# shield_2016.net
KiCad netlist of a schematic drawn in EAGLE
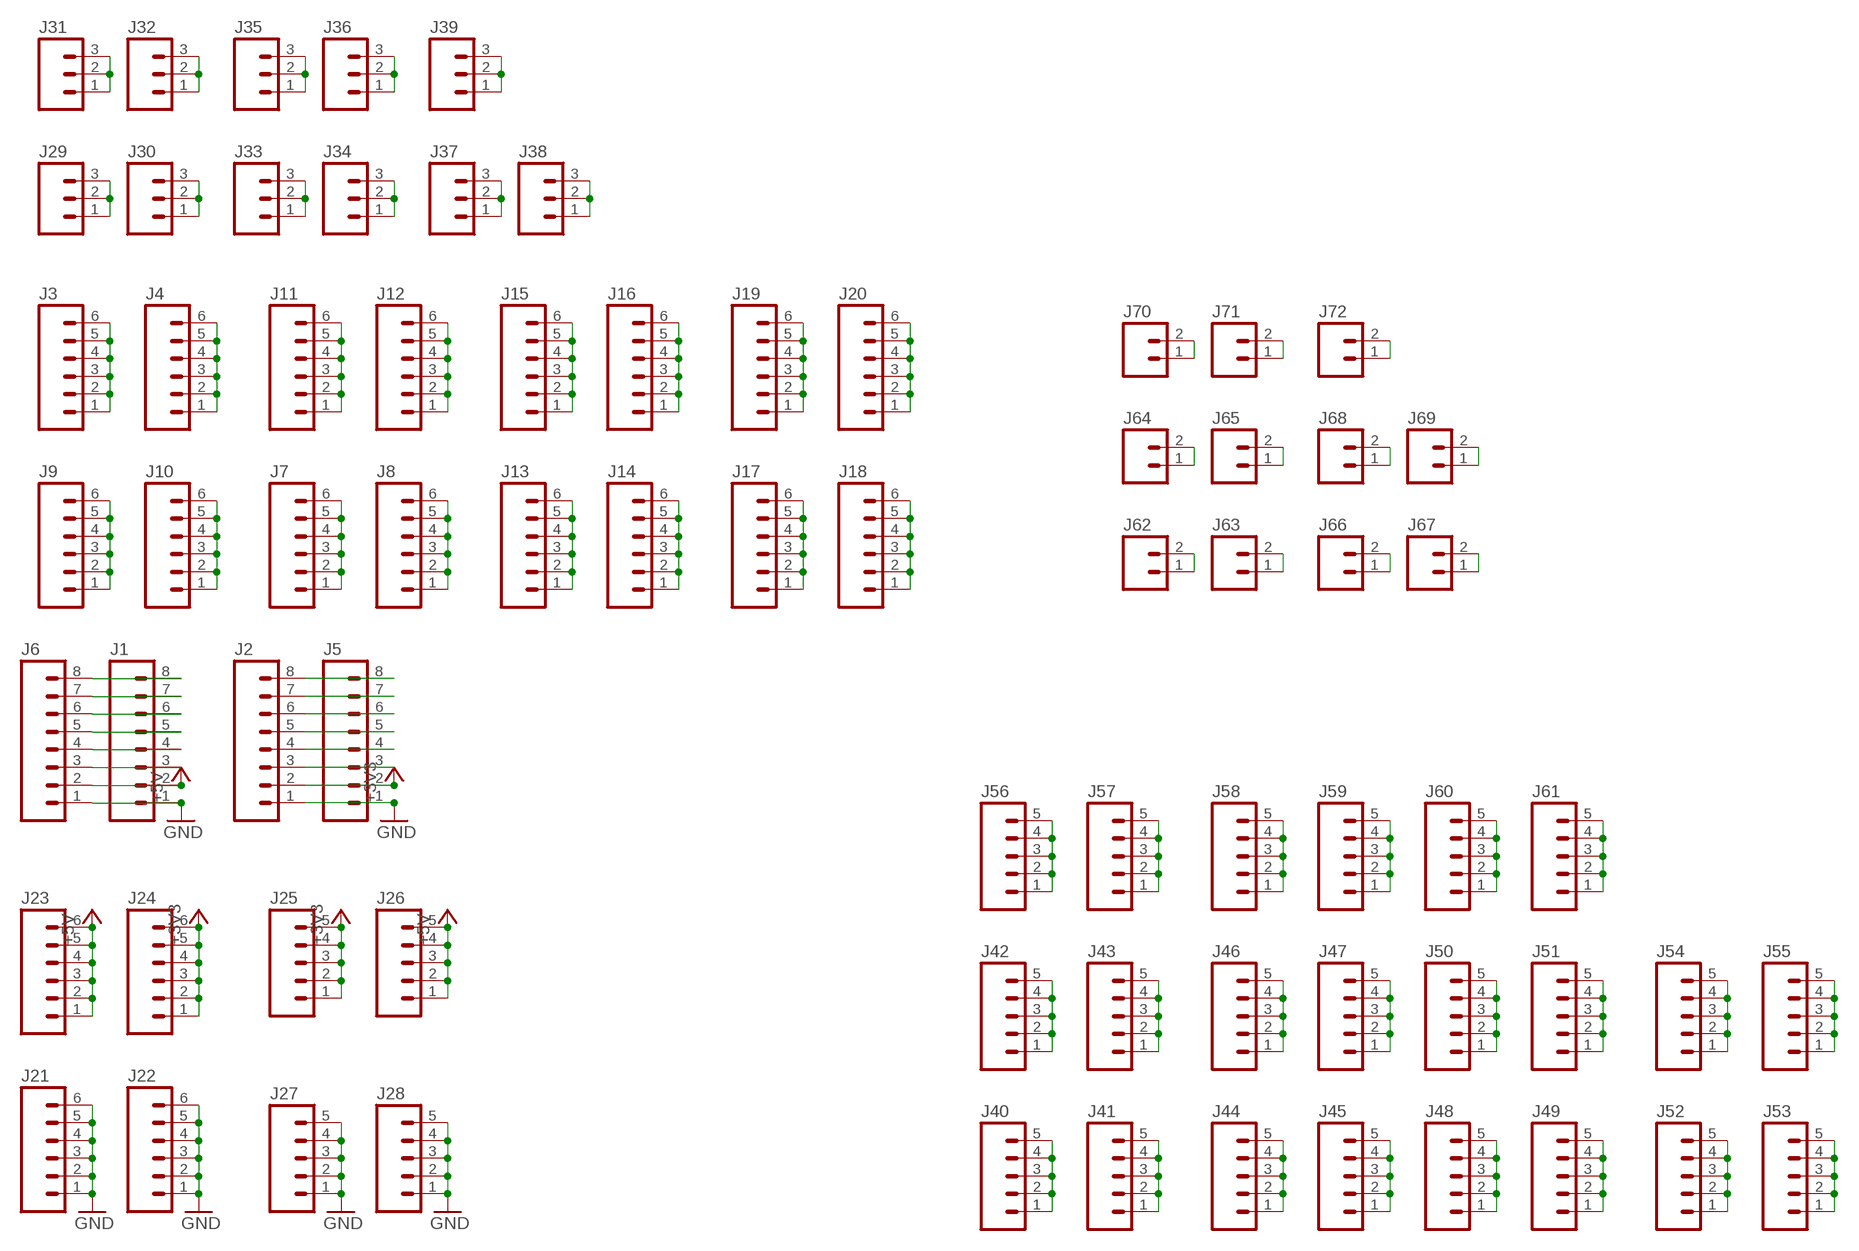
[diagram p0: schematic, sheet 1]

(export (version "E")
  (design (tool "Eeschema 10.0.6"))
  (components
    (comp (ref "J1")
      (value "M08")
      (footprint "eagle-import:1X08_ROUND")
      (libsource (lib "eagle-import") (part "M08"))
    )
    (comp (ref "J2")
      (value "M08")
      (footprint "eagle-import:1X08_ROUND")
      (libsource (lib "eagle-import") (part "M08"))
    )
    (comp (ref "J3")
      (value "M06SILK_FEMALE_PTH")
      (footprint "eagle-import:1X06")
      (libsource (lib "eagle-import") (part "M06SILK_FEMALE_PTH"))
    )
    (comp (ref "J4")
      (value "M06SILK_FEMALE_PTH")
      (footprint "eagle-import:1X06")
      (libsource (lib "eagle-import") (part "M06SILK_FEMALE_PTH"))
    )
    (comp (ref "J5")
      (value "M08")
      (footprint "eagle-import:1X08_ROUND")
      (libsource (lib "eagle-import") (part "M08"))
    )
    (comp (ref "J6")
      (value "M08")
      (footprint "eagle-import:1X08_ROUND")
      (libsource (lib "eagle-import") (part "M08"))
    )
    (comp (ref "J7")
      (value "M06SILK_FEMALE_PTH")
      (footprint "eagle-import:1X06")
      (libsource (lib "eagle-import") (part "M06SILK_FEMALE_PTH"))
    )
    (comp (ref "J8")
      (value "M06SILK_FEMALE_PTH")
      (footprint "eagle-import:1X06")
      (libsource (lib "eagle-import") (part "M06SILK_FEMALE_PTH"))
    )
    (comp (ref "J9")
      (value "M06SILK_FEMALE_PTH")
      (footprint "eagle-import:1X06")
      (libsource (lib "eagle-import") (part "M06SILK_FEMALE_PTH"))
    )
    (comp (ref "J10")
      (value "M06SILK_FEMALE_PTH")
      (footprint "eagle-import:1X06")
      (libsource (lib "eagle-import") (part "M06SILK_FEMALE_PTH"))
    )
    (comp (ref "J11")
      (value "M06SILK_FEMALE_PTH")
      (footprint "eagle-import:1X06")
      (libsource (lib "eagle-import") (part "M06SILK_FEMALE_PTH"))
    )
    (comp (ref "J12")
      (value "M06SILK_FEMALE_PTH")
      (footprint "eagle-import:1X06")
      (libsource (lib "eagle-import") (part "M06SILK_FEMALE_PTH"))
    )
    (comp (ref "J13")
      (value "M06SILK_FEMALE_PTH")
      (footprint "eagle-import:1X06")
      (libsource (lib "eagle-import") (part "M06SILK_FEMALE_PTH"))
    )
    (comp (ref "J14")
      (value "M06SILK_FEMALE_PTH")
      (footprint "eagle-import:1X06")
      (libsource (lib "eagle-import") (part "M06SILK_FEMALE_PTH"))
    )
    (comp (ref "J15")
      (value "M06SILK_FEMALE_PTH")
      (footprint "eagle-import:1X06")
      (libsource (lib "eagle-import") (part "M06SILK_FEMALE_PTH"))
    )
    (comp (ref "J16")
      (value "M06SILK_FEMALE_PTH")
      (footprint "eagle-import:1X06")
      (libsource (lib "eagle-import") (part "M06SILK_FEMALE_PTH"))
    )
    (comp (ref "J17")
      (value "M06SILK_FEMALE_PTH")
      (footprint "eagle-import:1X06")
      (libsource (lib "eagle-import") (part "M06SILK_FEMALE_PTH"))
    )
    (comp (ref "J18")
      (value "M06SILK_FEMALE_PTH")
      (footprint "eagle-import:1X06")
      (libsource (lib "eagle-import") (part "M06SILK_FEMALE_PTH"))
    )
    (comp (ref "J19")
      (value "M06SILK_FEMALE_PTH")
      (footprint "eagle-import:1X06")
      (libsource (lib "eagle-import") (part "M06SILK_FEMALE_PTH"))
    )
    (comp (ref "J20")
      (value "M06SILK_FEMALE_PTH")
      (footprint "eagle-import:1X06")
      (libsource (lib "eagle-import") (part "M06SILK_FEMALE_PTH"))
    )
    (comp (ref "J21")
      (value "M06SILK_FEMALE_PTH")
      (footprint "eagle-import:1X06")
      (libsource (lib "eagle-import") (part "M06SILK_FEMALE_PTH"))
    )
    (comp (ref "J22")
      (value "M06SILK_FEMALE_PTH")
      (footprint "eagle-import:1X06")
      (libsource (lib "eagle-import") (part "M06SILK_FEMALE_PTH"))
    )
    (comp (ref "J23")
      (value "M06SILK_FEMALE_PTH")
      (footprint "eagle-import:1X06")
      (libsource (lib "eagle-import") (part "M06SILK_FEMALE_PTH"))
    )
    (comp (ref "J24")
      (value "M06SILK_FEMALE_PTH")
      (footprint "eagle-import:1X06")
      (libsource (lib "eagle-import") (part "M06SILK_FEMALE_PTH"))
    )
    (comp (ref "J25")
      (value "M05PTH")
      (footprint "eagle-import:1X05")
      (libsource (lib "eagle-import") (part "M05PTH"))
    )
    (comp (ref "J26")
      (value "M05PTH")
      (footprint "eagle-import:1X05")
      (libsource (lib "eagle-import") (part "M05PTH"))
    )
    (comp (ref "J27")
      (value "M05PTH")
      (footprint "eagle-import:1X05")
      (libsource (lib "eagle-import") (part "M05PTH"))
    )
    (comp (ref "J28")
      (value "M05PTH")
      (footprint "eagle-import:1X05")
      (libsource (lib "eagle-import") (part "M05PTH"))
    )
    (comp (ref "J29")
      (value "M03PTH")
      (footprint "eagle-import:1X03")
      (libsource (lib "eagle-import") (part "M03PTH"))
    )
    (comp (ref "J30")
      (value "M03PTH")
      (footprint "eagle-import:1X03")
      (libsource (lib "eagle-import") (part "M03PTH"))
    )
    (comp (ref "J31")
      (value "M03PTH")
      (footprint "eagle-import:1X03")
      (libsource (lib "eagle-import") (part "M03PTH"))
    )
    (comp (ref "J32")
      (value "M03PTH")
      (footprint "eagle-import:1X03")
      (libsource (lib "eagle-import") (part "M03PTH"))
    )
    (comp (ref "J33")
      (value "M03PTH")
      (footprint "eagle-import:1X03")
      (libsource (lib "eagle-import") (part "M03PTH"))
    )
    (comp (ref "J34")
      (value "M03PTH")
      (footprint "eagle-import:1X03")
      (libsource (lib "eagle-import") (part "M03PTH"))
    )
    (comp (ref "J35")
      (value "M03PTH")
      (footprint "eagle-import:1X03")
      (libsource (lib "eagle-import") (part "M03PTH"))
    )
    (comp (ref "J36")
      (value "M03PTH")
      (footprint "eagle-import:1X03")
      (libsource (lib "eagle-import") (part "M03PTH"))
    )
    (comp (ref "J37")
      (value "M03PTH")
      (footprint "eagle-import:1X03")
      (libsource (lib "eagle-import") (part "M03PTH"))
    )
    (comp (ref "J38")
      (value "M03PTH")
      (footprint "eagle-import:1X03")
      (libsource (lib "eagle-import") (part "M03PTH"))
    )
    (comp (ref "J39")
      (value "M03PTH")
      (footprint "eagle-import:1X03")
      (libsource (lib "eagle-import") (part "M03PTH"))
    )
    (comp (ref "J40")
      (value "M05PTH")
      (footprint "eagle-import:1X05")
      (libsource (lib "eagle-import") (part "M05PTH"))
    )
    (comp (ref "J41")
      (value "M05PTH")
      (footprint "eagle-import:1X05")
      (libsource (lib "eagle-import") (part "M05PTH"))
    )
    (comp (ref "J42")
      (value "M05PTH")
      (footprint "eagle-import:1X05")
      (libsource (lib "eagle-import") (part "M05PTH"))
    )
    (comp (ref "J43")
      (value "M05PTH")
      (footprint "eagle-import:1X05")
      (libsource (lib "eagle-import") (part "M05PTH"))
    )
    (comp (ref "J44")
      (value "M05PTH")
      (footprint "eagle-import:1X05")
      (libsource (lib "eagle-import") (part "M05PTH"))
    )
    (comp (ref "J45")
      (value "M05PTH")
      (footprint "eagle-import:1X05")
      (libsource (lib "eagle-import") (part "M05PTH"))
    )
    (comp (ref "J46")
      (value "M05PTH")
      (footprint "eagle-import:1X05")
      (libsource (lib "eagle-import") (part "M05PTH"))
    )
    (comp (ref "J47")
      (value "M05PTH")
      (footprint "eagle-import:1X05")
      (libsource (lib "eagle-import") (part "M05PTH"))
    )
    (comp (ref "J48")
      (value "M05PTH")
      (footprint "eagle-import:1X05")
      (libsource (lib "eagle-import") (part "M05PTH"))
    )
    (comp (ref "J49")
      (value "M05PTH")
      (footprint "eagle-import:1X05")
      (libsource (lib "eagle-import") (part "M05PTH"))
    )
    (comp (ref "J50")
      (value "M05PTH")
      (footprint "eagle-import:1X05")
      (libsource (lib "eagle-import") (part "M05PTH"))
    )
    (comp (ref "J51")
      (value "M05PTH")
      (footprint "eagle-import:1X05")
      (libsource (lib "eagle-import") (part "M05PTH"))
    )
    (comp (ref "J52")
      (value "M05PTH")
      (footprint "eagle-import:1X05")
      (libsource (lib "eagle-import") (part "M05PTH"))
    )
    (comp (ref "J53")
      (value "M05PTH")
      (footprint "eagle-import:1X05")
      (libsource (lib "eagle-import") (part "M05PTH"))
    )
    (comp (ref "J54")
      (value "M05PTH")
      (footprint "eagle-import:1X05")
      (libsource (lib "eagle-import") (part "M05PTH"))
    )
    (comp (ref "J55")
      (value "M05PTH")
      (footprint "eagle-import:1X05")
      (libsource (lib "eagle-import") (part "M05PTH"))
    )
    (comp (ref "J56")
      (value "M05PTH")
      (footprint "eagle-import:1X05")
      (libsource (lib "eagle-import") (part "M05PTH"))
    )
    (comp (ref "J57")
      (value "M05PTH")
      (footprint "eagle-import:1X05")
      (libsource (lib "eagle-import") (part "M05PTH"))
    )
    (comp (ref "J58")
      (value "M05PTH")
      (footprint "eagle-import:1X05")
      (libsource (lib "eagle-import") (part "M05PTH"))
    )
    (comp (ref "J59")
      (value "M05PTH")
      (footprint "eagle-import:1X05")
      (libsource (lib "eagle-import") (part "M05PTH"))
    )
    (comp (ref "J60")
      (value "M05PTH")
      (footprint "eagle-import:1X05")
      (libsource (lib "eagle-import") (part "M05PTH"))
    )
    (comp (ref "J61")
      (value "M05PTH")
      (footprint "eagle-import:1X05")
      (libsource (lib "eagle-import") (part "M05PTH"))
    )
    (comp (ref "J62")
      (value "M02PTH")
      (footprint "eagle-import:1X02")
      (libsource (lib "eagle-import") (part "M02PTH"))
    )
    (comp (ref "J63")
      (value "M02PTH")
      (footprint "eagle-import:1X02")
      (libsource (lib "eagle-import") (part "M02PTH"))
    )
    (comp (ref "J64")
      (value "M02PTH")
      (footprint "eagle-import:1X02")
      (libsource (lib "eagle-import") (part "M02PTH"))
    )
    (comp (ref "J65")
      (value "M02PTH")
      (footprint "eagle-import:1X02")
      (libsource (lib "eagle-import") (part "M02PTH"))
    )
    (comp (ref "J66")
      (value "M02PTH")
      (footprint "eagle-import:1X02")
      (libsource (lib "eagle-import") (part "M02PTH"))
    )
    (comp (ref "J67")
      (value "M02PTH")
      (footprint "eagle-import:1X02")
      (libsource (lib "eagle-import") (part "M02PTH"))
    )
    (comp (ref "J68")
      (value "M02PTH")
      (footprint "eagle-import:1X02")
      (libsource (lib "eagle-import") (part "M02PTH"))
    )
    (comp (ref "J69")
      (value "M02PTH")
      (footprint "eagle-import:1X02")
      (libsource (lib "eagle-import") (part "M02PTH"))
    )
    (comp (ref "J70")
      (value "M02PTH")
      (footprint "eagle-import:1X02")
      (libsource (lib "eagle-import") (part "M02PTH"))
    )
    (comp (ref "J71")
      (value "M02PTH")
      (footprint "eagle-import:1X02")
      (libsource (lib "eagle-import") (part "M02PTH"))
    )
    (comp (ref "J72")
      (value "M02PTH")
      (footprint "eagle-import:1X02")
      (libsource (lib "eagle-import") (part "M02PTH"))
    )
  )
  (nets
    (net (code "1") (name "+3V3") (class "Default")
      (node (ref "J2") (pin "2") (pinfunction "2_2") (pintype "passive"))
      (node (ref "J24") (pin "1") (pinfunction "1_1") (pintype "passive"))
      (node (ref "J24") (pin "2") (pinfunction "2_2") (pintype "passive"))
      (node (ref "J24") (pin "3") (pinfunction "3_3") (pintype "passive"))
      (node (ref "J24") (pin "4") (pinfunction "4_4") (pintype "passive"))
      (node (ref "J24") (pin "5") (pinfunction "5_5") (pintype "passive"))
      (node (ref "J24") (pin "6") (pinfunction "6_6") (pintype "passive"))
      (node (ref "J25") (pin "1") (pinfunction "1_1") (pintype "passive"))
      (node (ref "J25") (pin "2") (pinfunction "2_2") (pintype "passive"))
      (node (ref "J25") (pin "3") (pinfunction "3_3") (pintype "passive"))
      (node (ref "J25") (pin "4") (pinfunction "4_4") (pintype "passive"))
      (node (ref "J25") (pin "5") (pinfunction "5_5") (pintype "passive"))
      (node (ref "J5") (pin "2") (pinfunction "2_2") (pintype "passive"))
    )
    (net (code "2") (name "+5V") (class "Default")
      (node (ref "J1") (pin "2") (pinfunction "2_2") (pintype "passive"))
      (node (ref "J23") (pin "1") (pinfunction "1_1") (pintype "passive"))
      (node (ref "J23") (pin "2") (pinfunction "2_2") (pintype "passive"))
      (node (ref "J23") (pin "3") (pinfunction "3_3") (pintype "passive"))
      (node (ref "J23") (pin "4") (pinfunction "4_4") (pintype "passive"))
      (node (ref "J23") (pin "5") (pinfunction "5_5") (pintype "passive"))
      (node (ref "J23") (pin "6") (pinfunction "6_6") (pintype "passive"))
      (node (ref "J26") (pin "1") (pinfunction "1_1") (pintype "passive"))
      (node (ref "J26") (pin "2") (pinfunction "2_2") (pintype "passive"))
      (node (ref "J26") (pin "3") (pinfunction "3_3") (pintype "passive"))
      (node (ref "J26") (pin "4") (pinfunction "4_4") (pintype "passive"))
      (node (ref "J26") (pin "5") (pinfunction "5_5") (pintype "passive"))
      (node (ref "J6") (pin "2") (pinfunction "2_2") (pintype "passive"))
    )
    (net (code "3") (name "GND") (class "Default")
      (node (ref "J1") (pin "1") (pinfunction "1_1") (pintype "passive"))
      (node (ref "J2") (pin "1") (pinfunction "1_1") (pintype "passive"))
      (node (ref "J21") (pin "1") (pinfunction "1_1") (pintype "passive"))
      (node (ref "J21") (pin "2") (pinfunction "2_2") (pintype "passive"))
      (node (ref "J21") (pin "3") (pinfunction "3_3") (pintype "passive"))
      (node (ref "J21") (pin "4") (pinfunction "4_4") (pintype "passive"))
      (node (ref "J21") (pin "5") (pinfunction "5_5") (pintype "passive"))
      (node (ref "J21") (pin "6") (pinfunction "6_6") (pintype "passive"))
      (node (ref "J22") (pin "1") (pinfunction "1_1") (pintype "passive"))
      (node (ref "J22") (pin "2") (pinfunction "2_2") (pintype "passive"))
      (node (ref "J22") (pin "3") (pinfunction "3_3") (pintype "passive"))
      (node (ref "J22") (pin "4") (pinfunction "4_4") (pintype "passive"))
      (node (ref "J22") (pin "5") (pinfunction "5_5") (pintype "passive"))
      (node (ref "J22") (pin "6") (pinfunction "6_6") (pintype "passive"))
      (node (ref "J27") (pin "1") (pinfunction "1_1") (pintype "passive"))
      (node (ref "J27") (pin "2") (pinfunction "2_2") (pintype "passive"))
      (node (ref "J27") (pin "3") (pinfunction "3_3") (pintype "passive"))
      (node (ref "J27") (pin "4") (pinfunction "4_4") (pintype "passive"))
      (node (ref "J27") (pin "5") (pinfunction "5_5") (pintype "passive"))
      (node (ref "J28") (pin "1") (pinfunction "1_1") (pintype "passive"))
      (node (ref "J28") (pin "2") (pinfunction "2_2") (pintype "passive"))
      (node (ref "J28") (pin "3") (pinfunction "3_3") (pintype "passive"))
      (node (ref "J28") (pin "4") (pinfunction "4_4") (pintype "passive"))
      (node (ref "J28") (pin "5") (pinfunction "5_5") (pintype "passive"))
      (node (ref "J5") (pin "1") (pinfunction "1_1") (pintype "passive"))
      (node (ref "J6") (pin "1") (pinfunction "1_1") (pintype "passive"))
    )
    (net (code "4") (name "Net-(J1-Pad3)") (class "Default")
      (node (ref "J1") (pin "3") (pinfunction "3_3") (pintype "passive"))
      (node (ref "J6") (pin "3") (pinfunction "3_3") (pintype "passive"))
    )
    (net (code "5") (name "Net-(J1-Pad4)") (class "Default")
      (node (ref "J1") (pin "4") (pinfunction "4_4") (pintype "passive"))
      (node (ref "J6") (pin "4") (pinfunction "4_4") (pintype "passive"))
    )
    (net (code "6") (name "Net-(J1-Pad5)") (class "Default")
      (node (ref "J1") (pin "5") (pinfunction "5_5") (pintype "passive"))
      (node (ref "J6") (pin "5") (pinfunction "5_5") (pintype "passive"))
    )
    (net (code "7") (name "Net-(J1-Pad6)") (class "Default")
      (node (ref "J1") (pin "6") (pinfunction "6_6") (pintype "passive"))
      (node (ref "J6") (pin "6") (pinfunction "6_6") (pintype "passive"))
    )
    (net (code "8") (name "Net-(J1-Pad7)") (class "Default")
      (node (ref "J1") (pin "7") (pinfunction "7_7") (pintype "passive"))
      (node (ref "J6") (pin "7") (pinfunction "7_7") (pintype "passive"))
    )
    (net (code "9") (name "Net-(J1-Pad8)") (class "Default")
      (node (ref "J1") (pin "8") (pinfunction "8_8") (pintype "passive"))
      (node (ref "J6") (pin "8") (pinfunction "8_8") (pintype "passive"))
    )
    (net (code "10") (name "Net-(J2-Pad3)") (class "Default")
      (node (ref "J2") (pin "3") (pinfunction "3_3") (pintype "passive"))
      (node (ref "J5") (pin "3") (pinfunction "3_3") (pintype "passive"))
    )
    (net (code "11") (name "Net-(J2-Pad4)") (class "Default")
      (node (ref "J2") (pin "4") (pinfunction "4_4") (pintype "passive"))
      (node (ref "J5") (pin "4") (pinfunction "4_4") (pintype "passive"))
    )
    (net (code "12") (name "Net-(J2-Pad5)") (class "Default")
      (node (ref "J2") (pin "5") (pinfunction "5_5") (pintype "passive"))
      (node (ref "J5") (pin "5") (pinfunction "5_5") (pintype "passive"))
    )
    (net (code "13") (name "Net-(J2-Pad6)") (class "Default")
      (node (ref "J2") (pin "6") (pinfunction "6_6") (pintype "passive"))
      (node (ref "J5") (pin "6") (pinfunction "6_6") (pintype "passive"))
    )
    (net (code "14") (name "Net-(J2-Pad7)") (class "Default")
      (node (ref "J2") (pin "7") (pinfunction "7_7") (pintype "passive"))
      (node (ref "J5") (pin "7") (pinfunction "7_7") (pintype "passive"))
    )
    (net (code "15") (name "Net-(J2-Pad8)") (class "Default")
      (node (ref "J2") (pin "8") (pinfunction "8_8") (pintype "passive"))
      (node (ref "J5") (pin "8") (pinfunction "8_8") (pintype "passive"))
    )
    (net (code "16") (name "Net-(J3-Pad1)") (class "Default")
      (node (ref "J3") (pin "1") (pinfunction "1_1") (pintype "passive"))
      (node (ref "J3") (pin "2") (pinfunction "2_2") (pintype "passive"))
      (node (ref "J3") (pin "3") (pinfunction "3_3") (pintype "passive"))
      (node (ref "J3") (pin "4") (pinfunction "4_4") (pintype "passive"))
      (node (ref "J3") (pin "5") (pinfunction "5_5") (pintype "passive"))
      (node (ref "J3") (pin "6") (pinfunction "6_6") (pintype "passive"))
    )
    (net (code "17") (name "Net-(J4-Pad1)") (class "Default")
      (node (ref "J4") (pin "1") (pinfunction "1_1") (pintype "passive"))
      (node (ref "J4") (pin "2") (pinfunction "2_2") (pintype "passive"))
      (node (ref "J4") (pin "3") (pinfunction "3_3") (pintype "passive"))
      (node (ref "J4") (pin "4") (pinfunction "4_4") (pintype "passive"))
      (node (ref "J4") (pin "5") (pinfunction "5_5") (pintype "passive"))
      (node (ref "J4") (pin "6") (pinfunction "6_6") (pintype "passive"))
    )
    (net (code "18") (name "Net-(J7-Pad1)") (class "Default")
      (node (ref "J7") (pin "1") (pinfunction "1_1") (pintype "passive"))
      (node (ref "J7") (pin "2") (pinfunction "2_2") (pintype "passive"))
      (node (ref "J7") (pin "3") (pinfunction "3_3") (pintype "passive"))
      (node (ref "J7") (pin "4") (pinfunction "4_4") (pintype "passive"))
      (node (ref "J7") (pin "5") (pinfunction "5_5") (pintype "passive"))
      (node (ref "J7") (pin "6") (pinfunction "6_6") (pintype "passive"))
    )
    (net (code "19") (name "Net-(J8-Pad1)") (class "Default")
      (node (ref "J8") (pin "1") (pinfunction "1_1") (pintype "passive"))
      (node (ref "J8") (pin "2") (pinfunction "2_2") (pintype "passive"))
      (node (ref "J8") (pin "3") (pinfunction "3_3") (pintype "passive"))
      (node (ref "J8") (pin "4") (pinfunction "4_4") (pintype "passive"))
      (node (ref "J8") (pin "5") (pinfunction "5_5") (pintype "passive"))
      (node (ref "J8") (pin "6") (pinfunction "6_6") (pintype "passive"))
    )
    (net (code "20") (name "Net-(J9-Pad1)") (class "Default")
      (node (ref "J9") (pin "1") (pinfunction "1_1") (pintype "passive"))
      (node (ref "J9") (pin "2") (pinfunction "2_2") (pintype "passive"))
      (node (ref "J9") (pin "3") (pinfunction "3_3") (pintype "passive"))
      (node (ref "J9") (pin "4") (pinfunction "4_4") (pintype "passive"))
      (node (ref "J9") (pin "5") (pinfunction "5_5") (pintype "passive"))
      (node (ref "J9") (pin "6") (pinfunction "6_6") (pintype "passive"))
    )
    (net (code "21") (name "Net-(J10-Pad1)") (class "Default")
      (node (ref "J10") (pin "1") (pinfunction "1_1") (pintype "passive"))
      (node (ref "J10") (pin "2") (pinfunction "2_2") (pintype "passive"))
      (node (ref "J10") (pin "3") (pinfunction "3_3") (pintype "passive"))
      (node (ref "J10") (pin "4") (pinfunction "4_4") (pintype "passive"))
      (node (ref "J10") (pin "5") (pinfunction "5_5") (pintype "passive"))
      (node (ref "J10") (pin "6") (pinfunction "6_6") (pintype "passive"))
    )
    (net (code "22") (name "Net-(J11-Pad1)") (class "Default")
      (node (ref "J11") (pin "1") (pinfunction "1_1") (pintype "passive"))
      (node (ref "J11") (pin "2") (pinfunction "2_2") (pintype "passive"))
      (node (ref "J11") (pin "3") (pinfunction "3_3") (pintype "passive"))
      (node (ref "J11") (pin "4") (pinfunction "4_4") (pintype "passive"))
      (node (ref "J11") (pin "5") (pinfunction "5_5") (pintype "passive"))
      (node (ref "J11") (pin "6") (pinfunction "6_6") (pintype "passive"))
    )
    (net (code "23") (name "Net-(J12-Pad1)") (class "Default")
      (node (ref "J12") (pin "1") (pinfunction "1_1") (pintype "passive"))
      (node (ref "J12") (pin "2") (pinfunction "2_2") (pintype "passive"))
      (node (ref "J12") (pin "3") (pinfunction "3_3") (pintype "passive"))
      (node (ref "J12") (pin "4") (pinfunction "4_4") (pintype "passive"))
      (node (ref "J12") (pin "5") (pinfunction "5_5") (pintype "passive"))
      (node (ref "J12") (pin "6") (pinfunction "6_6") (pintype "passive"))
    )
    (net (code "24") (name "Net-(J13-Pad1)") (class "Default")
      (node (ref "J13") (pin "1") (pinfunction "1_1") (pintype "passive"))
      (node (ref "J13") (pin "2") (pinfunction "2_2") (pintype "passive"))
      (node (ref "J13") (pin "3") (pinfunction "3_3") (pintype "passive"))
      (node (ref "J13") (pin "4") (pinfunction "4_4") (pintype "passive"))
      (node (ref "J13") (pin "5") (pinfunction "5_5") (pintype "passive"))
      (node (ref "J13") (pin "6") (pinfunction "6_6") (pintype "passive"))
    )
    (net (code "25") (name "Net-(J14-Pad1)") (class "Default")
      (node (ref "J14") (pin "1") (pinfunction "1_1") (pintype "passive"))
      (node (ref "J14") (pin "2") (pinfunction "2_2") (pintype "passive"))
      (node (ref "J14") (pin "3") (pinfunction "3_3") (pintype "passive"))
      (node (ref "J14") (pin "4") (pinfunction "4_4") (pintype "passive"))
      (node (ref "J14") (pin "5") (pinfunction "5_5") (pintype "passive"))
      (node (ref "J14") (pin "6") (pinfunction "6_6") (pintype "passive"))
    )
    (net (code "26") (name "Net-(J15-Pad1)") (class "Default")
      (node (ref "J15") (pin "1") (pinfunction "1_1") (pintype "passive"))
      (node (ref "J15") (pin "2") (pinfunction "2_2") (pintype "passive"))
      (node (ref "J15") (pin "3") (pinfunction "3_3") (pintype "passive"))
      (node (ref "J15") (pin "4") (pinfunction "4_4") (pintype "passive"))
      (node (ref "J15") (pin "5") (pinfunction "5_5") (pintype "passive"))
      (node (ref "J15") (pin "6") (pinfunction "6_6") (pintype "passive"))
    )
    (net (code "27") (name "Net-(J16-Pad1)") (class "Default")
      (node (ref "J16") (pin "1") (pinfunction "1_1") (pintype "passive"))
      (node (ref "J16") (pin "2") (pinfunction "2_2") (pintype "passive"))
      (node (ref "J16") (pin "3") (pinfunction "3_3") (pintype "passive"))
      (node (ref "J16") (pin "4") (pinfunction "4_4") (pintype "passive"))
      (node (ref "J16") (pin "5") (pinfunction "5_5") (pintype "passive"))
      (node (ref "J16") (pin "6") (pinfunction "6_6") (pintype "passive"))
    )
    (net (code "28") (name "Net-(J17-Pad1)") (class "Default")
      (node (ref "J17") (pin "1") (pinfunction "1_1") (pintype "passive"))
      (node (ref "J17") (pin "2") (pinfunction "2_2") (pintype "passive"))
      (node (ref "J17") (pin "3") (pinfunction "3_3") (pintype "passive"))
      (node (ref "J17") (pin "4") (pinfunction "4_4") (pintype "passive"))
      (node (ref "J17") (pin "5") (pinfunction "5_5") (pintype "passive"))
      (node (ref "J17") (pin "6") (pinfunction "6_6") (pintype "passive"))
    )
    (net (code "29") (name "Net-(J18-Pad1)") (class "Default")
      (node (ref "J18") (pin "1") (pinfunction "1_1") (pintype "passive"))
      (node (ref "J18") (pin "2") (pinfunction "2_2") (pintype "passive"))
      (node (ref "J18") (pin "3") (pinfunction "3_3") (pintype "passive"))
      (node (ref "J18") (pin "4") (pinfunction "4_4") (pintype "passive"))
      (node (ref "J18") (pin "5") (pinfunction "5_5") (pintype "passive"))
      (node (ref "J18") (pin "6") (pinfunction "6_6") (pintype "passive"))
    )
    (net (code "30") (name "Net-(J19-Pad1)") (class "Default")
      (node (ref "J19") (pin "1") (pinfunction "1_1") (pintype "passive"))
      (node (ref "J19") (pin "2") (pinfunction "2_2") (pintype "passive"))
      (node (ref "J19") (pin "3") (pinfunction "3_3") (pintype "passive"))
      (node (ref "J19") (pin "4") (pinfunction "4_4") (pintype "passive"))
      (node (ref "J19") (pin "5") (pinfunction "5_5") (pintype "passive"))
      (node (ref "J19") (pin "6") (pinfunction "6_6") (pintype "passive"))
    )
    (net (code "31") (name "Net-(J20-Pad1)") (class "Default")
      (node (ref "J20") (pin "1") (pinfunction "1_1") (pintype "passive"))
      (node (ref "J20") (pin "2") (pinfunction "2_2") (pintype "passive"))
      (node (ref "J20") (pin "3") (pinfunction "3_3") (pintype "passive"))
      (node (ref "J20") (pin "4") (pinfunction "4_4") (pintype "passive"))
      (node (ref "J20") (pin "5") (pinfunction "5_5") (pintype "passive"))
      (node (ref "J20") (pin "6") (pinfunction "6_6") (pintype "passive"))
    )
    (net (code "32") (name "Net-(J29-Pad1)") (class "Default")
      (node (ref "J29") (pin "1") (pinfunction "1_1") (pintype "passive"))
      (node (ref "J29") (pin "2") (pinfunction "2_2") (pintype "passive"))
      (node (ref "J29") (pin "3") (pinfunction "3_3") (pintype "passive"))
    )
    (net (code "33") (name "Net-(J30-Pad1)") (class "Default")
      (node (ref "J30") (pin "1") (pinfunction "1_1") (pintype "passive"))
      (node (ref "J30") (pin "2") (pinfunction "2_2") (pintype "passive"))
      (node (ref "J30") (pin "3") (pinfunction "3_3") (pintype "passive"))
    )
    (net (code "34") (name "Net-(J31-Pad1)") (class "Default")
      (node (ref "J31") (pin "1") (pinfunction "1_1") (pintype "passive"))
      (node (ref "J31") (pin "2") (pinfunction "2_2") (pintype "passive"))
      (node (ref "J31") (pin "3") (pinfunction "3_3") (pintype "passive"))
    )
    (net (code "35") (name "Net-(J32-Pad1)") (class "Default")
      (node (ref "J32") (pin "1") (pinfunction "1_1") (pintype "passive"))
      (node (ref "J32") (pin "2") (pinfunction "2_2") (pintype "passive"))
      (node (ref "J32") (pin "3") (pinfunction "3_3") (pintype "passive"))
    )
    (net (code "36") (name "Net-(J33-Pad1)") (class "Default")
      (node (ref "J33") (pin "1") (pinfunction "1_1") (pintype "passive"))
      (node (ref "J33") (pin "2") (pinfunction "2_2") (pintype "passive"))
      (node (ref "J33") (pin "3") (pinfunction "3_3") (pintype "passive"))
    )
    (net (code "37") (name "Net-(J34-Pad1)") (class "Default")
      (node (ref "J34") (pin "1") (pinfunction "1_1") (pintype "passive"))
      (node (ref "J34") (pin "2") (pinfunction "2_2") (pintype "passive"))
      (node (ref "J34") (pin "3") (pinfunction "3_3") (pintype "passive"))
    )
    (net (code "38") (name "Net-(J35-Pad1)") (class "Default")
      (node (ref "J35") (pin "1") (pinfunction "1_1") (pintype "passive"))
      (node (ref "J35") (pin "2") (pinfunction "2_2") (pintype "passive"))
      (node (ref "J35") (pin "3") (pinfunction "3_3") (pintype "passive"))
    )
    (net (code "39") (name "Net-(J36-Pad1)") (class "Default")
      (node (ref "J36") (pin "1") (pinfunction "1_1") (pintype "passive"))
      (node (ref "J36") (pin "2") (pinfunction "2_2") (pintype "passive"))
      (node (ref "J36") (pin "3") (pinfunction "3_3") (pintype "passive"))
    )
    (net (code "40") (name "Net-(J37-Pad1)") (class "Default")
      (node (ref "J37") (pin "1") (pinfunction "1_1") (pintype "passive"))
      (node (ref "J37") (pin "2") (pinfunction "2_2") (pintype "passive"))
      (node (ref "J37") (pin "3") (pinfunction "3_3") (pintype "passive"))
    )
    (net (code "41") (name "Net-(J38-Pad1)") (class "Default")
      (node (ref "J38") (pin "1") (pinfunction "1_1") (pintype "passive"))
      (node (ref "J38") (pin "2") (pinfunction "2_2") (pintype "passive"))
      (node (ref "J38") (pin "3") (pinfunction "3_3") (pintype "passive"))
    )
    (net (code "42") (name "Net-(J39-Pad1)") (class "Default")
      (node (ref "J39") (pin "1") (pinfunction "1_1") (pintype "passive"))
      (node (ref "J39") (pin "2") (pinfunction "2_2") (pintype "passive"))
      (node (ref "J39") (pin "3") (pinfunction "3_3") (pintype "passive"))
    )
    (net (code "43") (name "Net-(J40-Pad1)") (class "Default")
      (node (ref "J40") (pin "1") (pinfunction "1_1") (pintype "passive"))
      (node (ref "J40") (pin "2") (pinfunction "2_2") (pintype "passive"))
      (node (ref "J40") (pin "3") (pinfunction "3_3") (pintype "passive"))
      (node (ref "J40") (pin "4") (pinfunction "4_4") (pintype "passive"))
      (node (ref "J40") (pin "5") (pinfunction "5_5") (pintype "passive"))
    )
    (net (code "44") (name "Net-(J41-Pad1)") (class "Default")
      (node (ref "J41") (pin "1") (pinfunction "1_1") (pintype "passive"))
      (node (ref "J41") (pin "2") (pinfunction "2_2") (pintype "passive"))
      (node (ref "J41") (pin "3") (pinfunction "3_3") (pintype "passive"))
      (node (ref "J41") (pin "4") (pinfunction "4_4") (pintype "passive"))
      (node (ref "J41") (pin "5") (pinfunction "5_5") (pintype "passive"))
    )
    (net (code "45") (name "Net-(J42-Pad1)") (class "Default")
      (node (ref "J42") (pin "1") (pinfunction "1_1") (pintype "passive"))
      (node (ref "J42") (pin "2") (pinfunction "2_2") (pintype "passive"))
      (node (ref "J42") (pin "3") (pinfunction "3_3") (pintype "passive"))
      (node (ref "J42") (pin "4") (pinfunction "4_4") (pintype "passive"))
      (node (ref "J42") (pin "5") (pinfunction "5_5") (pintype "passive"))
    )
    (net (code "46") (name "Net-(J43-Pad1)") (class "Default")
      (node (ref "J43") (pin "1") (pinfunction "1_1") (pintype "passive"))
      (node (ref "J43") (pin "2") (pinfunction "2_2") (pintype "passive"))
      (node (ref "J43") (pin "3") (pinfunction "3_3") (pintype "passive"))
      (node (ref "J43") (pin "4") (pinfunction "4_4") (pintype "passive"))
      (node (ref "J43") (pin "5") (pinfunction "5_5") (pintype "passive"))
    )
    (net (code "47") (name "Net-(J44-Pad1)") (class "Default")
      (node (ref "J44") (pin "1") (pinfunction "1_1") (pintype "passive"))
      (node (ref "J44") (pin "2") (pinfunction "2_2") (pintype "passive"))
      (node (ref "J44") (pin "3") (pinfunction "3_3") (pintype "passive"))
      (node (ref "J44") (pin "4") (pinfunction "4_4") (pintype "passive"))
      (node (ref "J44") (pin "5") (pinfunction "5_5") (pintype "passive"))
    )
    (net (code "48") (name "Net-(J45-Pad1)") (class "Default")
      (node (ref "J45") (pin "1") (pinfunction "1_1") (pintype "passive"))
      (node (ref "J45") (pin "2") (pinfunction "2_2") (pintype "passive"))
      (node (ref "J45") (pin "3") (pinfunction "3_3") (pintype "passive"))
      (node (ref "J45") (pin "4") (pinfunction "4_4") (pintype "passive"))
      (node (ref "J45") (pin "5") (pinfunction "5_5") (pintype "passive"))
    )
    (net (code "49") (name "Net-(J46-Pad1)") (class "Default")
      (node (ref "J46") (pin "1") (pinfunction "1_1") (pintype "passive"))
      (node (ref "J46") (pin "2") (pinfunction "2_2") (pintype "passive"))
      (node (ref "J46") (pin "3") (pinfunction "3_3") (pintype "passive"))
      (node (ref "J46") (pin "4") (pinfunction "4_4") (pintype "passive"))
      (node (ref "J46") (pin "5") (pinfunction "5_5") (pintype "passive"))
    )
    (net (code "50") (name "Net-(J47-Pad1)") (class "Default")
      (node (ref "J47") (pin "1") (pinfunction "1_1") (pintype "passive"))
      (node (ref "J47") (pin "2") (pinfunction "2_2") (pintype "passive"))
      (node (ref "J47") (pin "3") (pinfunction "3_3") (pintype "passive"))
      (node (ref "J47") (pin "4") (pinfunction "4_4") (pintype "passive"))
      (node (ref "J47") (pin "5") (pinfunction "5_5") (pintype "passive"))
    )
    (net (code "51") (name "Net-(J48-Pad1)") (class "Default")
      (node (ref "J48") (pin "1") (pinfunction "1_1") (pintype "passive"))
      (node (ref "J48") (pin "2") (pinfunction "2_2") (pintype "passive"))
      (node (ref "J48") (pin "3") (pinfunction "3_3") (pintype "passive"))
      (node (ref "J48") (pin "4") (pinfunction "4_4") (pintype "passive"))
      (node (ref "J48") (pin "5") (pinfunction "5_5") (pintype "passive"))
    )
    (net (code "52") (name "Net-(J49-Pad1)") (class "Default")
      (node (ref "J49") (pin "1") (pinfunction "1_1") (pintype "passive"))
      (node (ref "J49") (pin "2") (pinfunction "2_2") (pintype "passive"))
      (node (ref "J49") (pin "3") (pinfunction "3_3") (pintype "passive"))
      (node (ref "J49") (pin "4") (pinfunction "4_4") (pintype "passive"))
      (node (ref "J49") (pin "5") (pinfunction "5_5") (pintype "passive"))
    )
    (net (code "53") (name "Net-(J50-Pad1)") (class "Default")
      (node (ref "J50") (pin "1") (pinfunction "1_1") (pintype "passive"))
      (node (ref "J50") (pin "2") (pinfunction "2_2") (pintype "passive"))
      (node (ref "J50") (pin "3") (pinfunction "3_3") (pintype "passive"))
      (node (ref "J50") (pin "4") (pinfunction "4_4") (pintype "passive"))
      (node (ref "J50") (pin "5") (pinfunction "5_5") (pintype "passive"))
    )
    (net (code "54") (name "Net-(J51-Pad1)") (class "Default")
      (node (ref "J51") (pin "1") (pinfunction "1_1") (pintype "passive"))
      (node (ref "J51") (pin "2") (pinfunction "2_2") (pintype "passive"))
      (node (ref "J51") (pin "3") (pinfunction "3_3") (pintype "passive"))
      (node (ref "J51") (pin "4") (pinfunction "4_4") (pintype "passive"))
      (node (ref "J51") (pin "5") (pinfunction "5_5") (pintype "passive"))
    )
    (net (code "55") (name "Net-(J52-Pad1)") (class "Default")
      (node (ref "J52") (pin "1") (pinfunction "1_1") (pintype "passive"))
      (node (ref "J52") (pin "2") (pinfunction "2_2") (pintype "passive"))
      (node (ref "J52") (pin "3") (pinfunction "3_3") (pintype "passive"))
      (node (ref "J52") (pin "4") (pinfunction "4_4") (pintype "passive"))
      (node (ref "J52") (pin "5") (pinfunction "5_5") (pintype "passive"))
    )
    (net (code "56") (name "Net-(J53-Pad1)") (class "Default")
      (node (ref "J53") (pin "1") (pinfunction "1_1") (pintype "passive"))
      (node (ref "J53") (pin "2") (pinfunction "2_2") (pintype "passive"))
      (node (ref "J53") (pin "3") (pinfunction "3_3") (pintype "passive"))
      (node (ref "J53") (pin "4") (pinfunction "4_4") (pintype "passive"))
      (node (ref "J53") (pin "5") (pinfunction "5_5") (pintype "passive"))
    )
    (net (code "57") (name "Net-(J54-Pad1)") (class "Default")
      (node (ref "J54") (pin "1") (pinfunction "1_1") (pintype "passive"))
      (node (ref "J54") (pin "2") (pinfunction "2_2") (pintype "passive"))
      (node (ref "J54") (pin "3") (pinfunction "3_3") (pintype "passive"))
      (node (ref "J54") (pin "4") (pinfunction "4_4") (pintype "passive"))
      (node (ref "J54") (pin "5") (pinfunction "5_5") (pintype "passive"))
    )
    (net (code "58") (name "Net-(J55-Pad1)") (class "Default")
      (node (ref "J55") (pin "1") (pinfunction "1_1") (pintype "passive"))
      (node (ref "J55") (pin "2") (pinfunction "2_2") (pintype "passive"))
      (node (ref "J55") (pin "3") (pinfunction "3_3") (pintype "passive"))
      (node (ref "J55") (pin "4") (pinfunction "4_4") (pintype "passive"))
      (node (ref "J55") (pin "5") (pinfunction "5_5") (pintype "passive"))
    )
    (net (code "59") (name "Net-(J56-Pad1)") (class "Default")
      (node (ref "J56") (pin "1") (pinfunction "1_1") (pintype "passive"))
      (node (ref "J56") (pin "2") (pinfunction "2_2") (pintype "passive"))
      (node (ref "J56") (pin "3") (pinfunction "3_3") (pintype "passive"))
      (node (ref "J56") (pin "4") (pinfunction "4_4") (pintype "passive"))
      (node (ref "J56") (pin "5") (pinfunction "5_5") (pintype "passive"))
    )
    (net (code "60") (name "Net-(J57-Pad1)") (class "Default")
      (node (ref "J57") (pin "1") (pinfunction "1_1") (pintype "passive"))
      (node (ref "J57") (pin "2") (pinfunction "2_2") (pintype "passive"))
      (node (ref "J57") (pin "3") (pinfunction "3_3") (pintype "passive"))
      (node (ref "J57") (pin "4") (pinfunction "4_4") (pintype "passive"))
      (node (ref "J57") (pin "5") (pinfunction "5_5") (pintype "passive"))
    )
    (net (code "61") (name "Net-(J58-Pad1)") (class "Default")
      (node (ref "J58") (pin "1") (pinfunction "1_1") (pintype "passive"))
      (node (ref "J58") (pin "2") (pinfunction "2_2") (pintype "passive"))
      (node (ref "J58") (pin "3") (pinfunction "3_3") (pintype "passive"))
      (node (ref "J58") (pin "4") (pinfunction "4_4") (pintype "passive"))
      (node (ref "J58") (pin "5") (pinfunction "5_5") (pintype "passive"))
    )
    (net (code "62") (name "Net-(J59-Pad1)") (class "Default")
      (node (ref "J59") (pin "1") (pinfunction "1_1") (pintype "passive"))
      (node (ref "J59") (pin "2") (pinfunction "2_2") (pintype "passive"))
      (node (ref "J59") (pin "3") (pinfunction "3_3") (pintype "passive"))
      (node (ref "J59") (pin "4") (pinfunction "4_4") (pintype "passive"))
      (node (ref "J59") (pin "5") (pinfunction "5_5") (pintype "passive"))
    )
    (net (code "63") (name "Net-(J60-Pad1)") (class "Default")
      (node (ref "J60") (pin "1") (pinfunction "1_1") (pintype "passive"))
      (node (ref "J60") (pin "2") (pinfunction "2_2") (pintype "passive"))
      (node (ref "J60") (pin "3") (pinfunction "3_3") (pintype "passive"))
      (node (ref "J60") (pin "4") (pinfunction "4_4") (pintype "passive"))
      (node (ref "J60") (pin "5") (pinfunction "5_5") (pintype "passive"))
    )
    (net (code "64") (name "Net-(J61-Pad1)") (class "Default")
      (node (ref "J61") (pin "1") (pinfunction "1_1") (pintype "passive"))
      (node (ref "J61") (pin "2") (pinfunction "2_2") (pintype "passive"))
      (node (ref "J61") (pin "3") (pinfunction "3_3") (pintype "passive"))
      (node (ref "J61") (pin "4") (pinfunction "4_4") (pintype "passive"))
      (node (ref "J61") (pin "5") (pinfunction "5_5") (pintype "passive"))
    )
    (net (code "65") (name "Net-(J62-Pad1)") (class "Default")
      (node (ref "J62") (pin "1") (pinfunction "1_1") (pintype "passive"))
      (node (ref "J62") (pin "2") (pinfunction "2_2") (pintype "passive"))
    )
    (net (code "66") (name "Net-(J63-Pad1)") (class "Default")
      (node (ref "J63") (pin "1") (pinfunction "1_1") (pintype "passive"))
      (node (ref "J63") (pin "2") (pinfunction "2_2") (pintype "passive"))
    )
    (net (code "67") (name "Net-(J64-Pad1)") (class "Default")
      (node (ref "J64") (pin "1") (pinfunction "1_1") (pintype "passive"))
      (node (ref "J64") (pin "2") (pinfunction "2_2") (pintype "passive"))
    )
    (net (code "68") (name "Net-(J65-Pad1)") (class "Default")
      (node (ref "J65") (pin "1") (pinfunction "1_1") (pintype "passive"))
      (node (ref "J65") (pin "2") (pinfunction "2_2") (pintype "passive"))
    )
    (net (code "69") (name "Net-(J66-Pad1)") (class "Default")
      (node (ref "J66") (pin "1") (pinfunction "1_1") (pintype "passive"))
      (node (ref "J66") (pin "2") (pinfunction "2_2") (pintype "passive"))
    )
    (net (code "70") (name "Net-(J67-Pad1)") (class "Default")
      (node (ref "J67") (pin "1") (pinfunction "1_1") (pintype "passive"))
      (node (ref "J67") (pin "2") (pinfunction "2_2") (pintype "passive"))
    )
    (net (code "71") (name "Net-(J68-Pad1)") (class "Default")
      (node (ref "J68") (pin "1") (pinfunction "1_1") (pintype "passive"))
      (node (ref "J68") (pin "2") (pinfunction "2_2") (pintype "passive"))
    )
    (net (code "72") (name "Net-(J69-Pad1)") (class "Default")
      (node (ref "J69") (pin "1") (pinfunction "1_1") (pintype "passive"))
      (node (ref "J69") (pin "2") (pinfunction "2_2") (pintype "passive"))
    )
    (net (code "73") (name "Net-(J70-Pad1)") (class "Default")
      (node (ref "J70") (pin "1") (pinfunction "1_1") (pintype "passive"))
      (node (ref "J70") (pin "2") (pinfunction "2_2") (pintype "passive"))
    )
    (net (code "74") (name "Net-(J71-Pad1)") (class "Default")
      (node (ref "J71") (pin "1") (pinfunction "1_1") (pintype "passive"))
      (node (ref "J71") (pin "2") (pinfunction "2_2") (pintype "passive"))
    )
    (net (code "75") (name "Net-(J72-Pad1)") (class "Default")
      (node (ref "J72") (pin "1") (pinfunction "1_1") (pintype "passive"))
      (node (ref "J72") (pin "2") (pinfunction "2_2") (pintype "passive"))
    )
  )
)
